# Power.net
KiCad netlist of a schematic drawn in Altium Designer
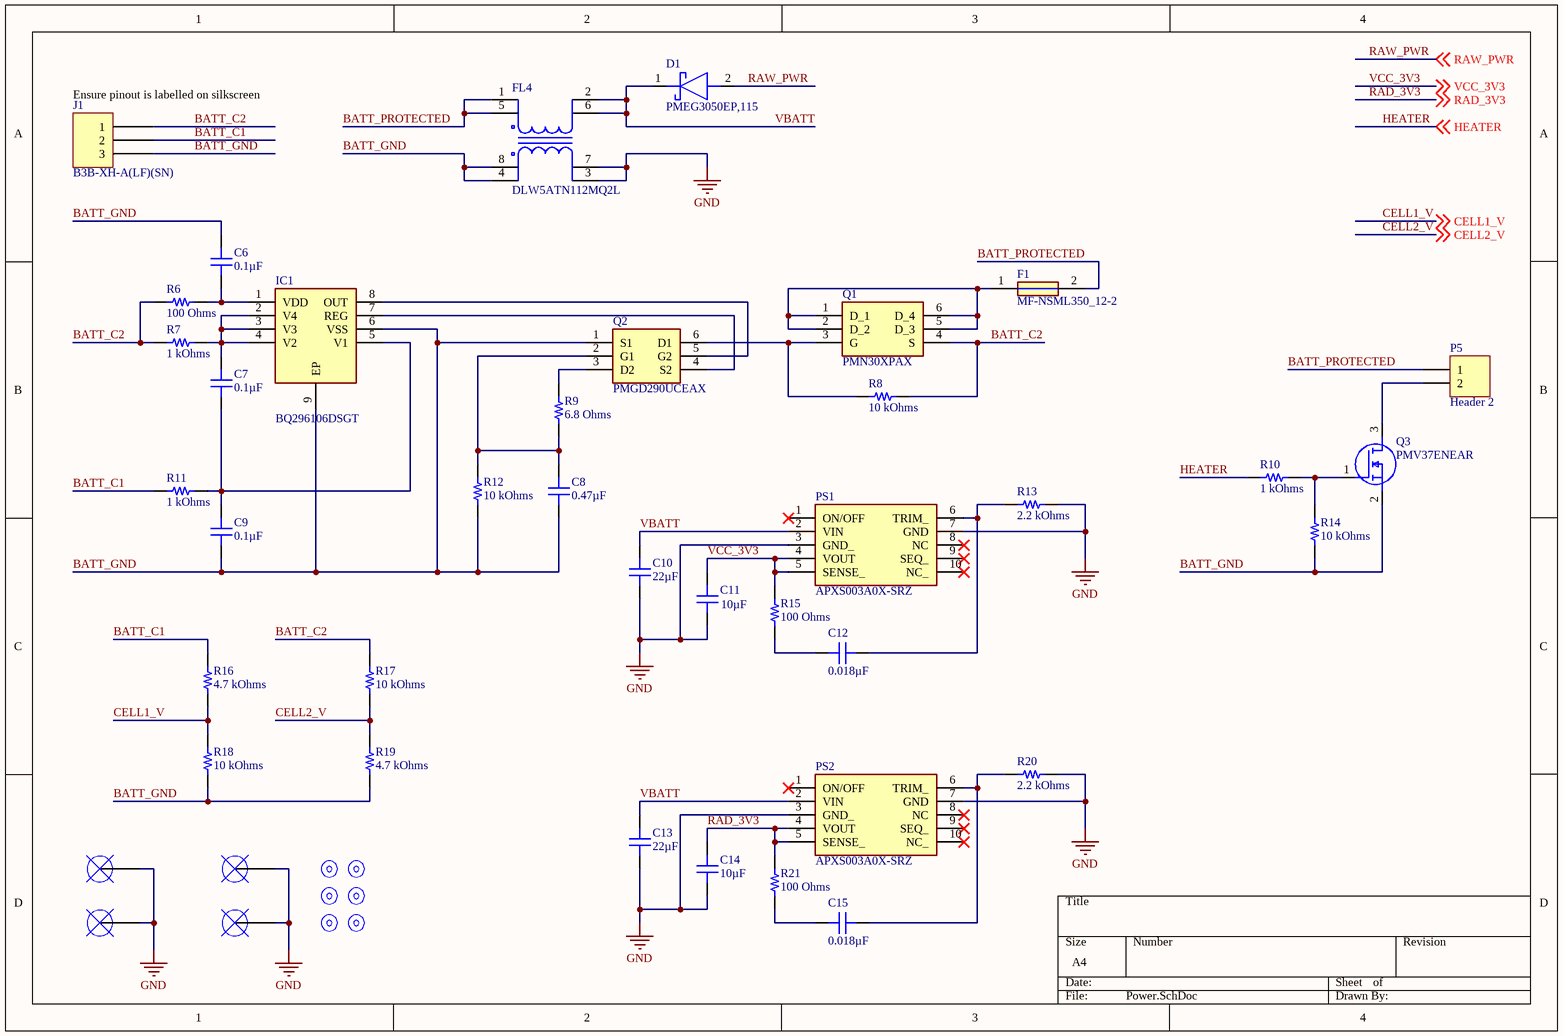
[diagram p0: Power.SchDoc]

(export (version "E")
  (design (tool "Eeschema 10.0.6"))
  (components
    (comp (ref "C6")
      (value "0.1µF")
      (footprint "CAP 0402_1005")
      (description "CAP CER 0.1UF 6.3V X5R 0402")
      (fields (field (name "PART NUMBER") "C0402C104K9PACTU") (field (name "MANUFACTURER") "KEMET"))
      (libsource (lib "Celestial Altium Library - altium_library") (part "Capacitor"))
    )
    (comp (ref "C7")
      (value "0.1µF")
      (footprint "CAP 0402_1005")
      (description "CAP CER 0.1UF 6.3V X5R 0402")
      (fields (field (name "PART NUMBER") "C0402C104K9PACTU") (field (name "MANUFACTURER") "KEMET"))
      (libsource (lib "Celestial Altium Library - altium_library") (part "Capacitor"))
    )
    (comp (ref "C8")
      (value "0.47µF")
      (footprint "CAP 0402_1005")
      (description "CAP CER 0.47UF 25V X5R 0402")
      (fields
        (field (name "PART NUMBER") "C1005X5R1E474K050BE")
        (field (name "MANUFACTURER") "TDK Corporation")
      )
      (libsource (lib "Celestial Altium Library - altium_library") (part "Capacitor"))
    )
    (comp (ref "C9")
      (value "0.1µF")
      (footprint "CAP 0402_1005")
      (description "CAP CER 0.1UF 6.3V X5R 0402")
      (fields (field (name "PART NUMBER") "C0402C104K9PACTU") (field (name "MANUFACTURER") "KEMET"))
      (libsource (lib "Celestial Altium Library - altium_library") (part "Capacitor"))
    )
    (comp (ref "C10")
      (value "22µF")
      (footprint "CAP 0805_2012")
      (description "CAP CER 22UF 16V X6S 0805")
      (fields
        (field (name "PART NUMBER") "C2012X6S1C226M125AC")
        (field (name "MANUFACTURER") "TDK Corporation")
      )
      (libsource (lib "Celestial Altium Library - altium_library") (part "Capacitor"))
    )
    (comp (ref "C11")
      (value "10µF")
      (footprint "CAP 0402_1005")
      (description "CAP CER 10UF 6.3V X5R 0402")
      (fields (field (name "PART NUMBER") "C0402C106M9PAC7867") (field (name "MANUFACTURER") "KEMET"))
      (libsource (lib "Celestial Altium Library - altium_library") (part "Capacitor"))
    )
    (comp (ref "C12")
      (value "0.018µF")
      (footprint "CAP 0402_1005")
      (description "CAP CER 0.018UF 25V X7R 0402")
      (fields (field (name "PART NUMBER") "CC0402KRX7R8BB183") (field (name "MANUFACTURER") "Yageo"))
      (libsource (lib "Celestial Altium Library - altium_library") (part "Capacitor"))
    )
    (comp (ref "C13")
      (value "22µF")
      (footprint "CAP 0805_2012")
      (description "CAP CER 22UF 16V X6S 0805")
      (fields
        (field (name "PART NUMBER") "C2012X6S1C226M125AC")
        (field (name "MANUFACTURER") "TDK Corporation")
      )
      (libsource (lib "Celestial Altium Library - altium_library") (part "Capacitor"))
    )
    (comp (ref "C14")
      (value "10µF")
      (footprint "CAP 0402_1005")
      (description "CAP CER 10UF 6.3V X5R 0402")
      (fields (field (name "PART NUMBER") "C0402C106M9PAC7867") (field (name "MANUFACTURER") "KEMET"))
      (libsource (lib "Celestial Altium Library - altium_library") (part "Capacitor"))
    )
    (comp (ref "C15")
      (value "0.018µF")
      (footprint "CAP 0402_1005")
      (description "CAP CER 0.018UF 25V X7R 0402")
      (fields (field (name "PART NUMBER") "CC0402KRX7R8BB183") (field (name "MANUFACTURER") "Yageo"))
      (libsource (lib "Celestial Altium Library - altium_library") (part "Capacitor"))
    )
    (comp (ref "D1")
      (value "PMEG3050EP,115")
      (footprint "SamacSys:PMEG3050EP115")
      (description "Schottky Diode")
      (libsource (lib "*") (part "PMEG3050EP,115"))
    )
    (comp (ref "F1")
      (value "MF-NSML350_12-2")
      (footprint "SamacSys:FUSC3216X140N")
      (description "Fuse")
      (fields (field (name "MANUFACTURER_PART_NUMBER") "MF-NSML350/12-2"))
      (libsource (lib "*") (part "MF-NSML350_12-2"))
    )
    (comp (ref "FL4")
      (value "DLW5ATN112MQ2L")
      (footprint "SamacSys:DLW5BSN302SQ2L")
      (description "Filter")
      (fields (field (name "MOUSER2 PART NUMBER") "81-DLW5ATN112MQ2L"))
      (libsource (lib "*") (part "DLW5ATN112MQ2L"))
    )
    (comp (ref "FM1")
      (value "1mm")
      (footprint "FIDUCIAL_MARK_ROUND")
      (description "Fiducial mark, width 1mm, clearance 3mm")
      (libsource (lib "VITA_57_FMC") (part "Fiducial_Mark"))
    )
    (comp (ref "FM2")
      (value "1mm")
      (footprint "FIDUCIAL_MARK_ROUND")
      (description "Fiducial mark, width 1mm, clearance 3mm")
      (libsource (lib "VITA_57_FMC") (part "Fiducial_Mark"))
    )
    (comp (ref "FM3")
      (value "1mm")
      (footprint "FIDUCIAL_MARK_ROUND")
      (description "Fiducial mark, width 1mm, clearance 3mm")
      (libsource (lib "VITA_57_FMC") (part "Fiducial_Mark"))
    )
    (comp (ref "FM4")
      (value "1mm")
      (footprint "FIDUCIAL_MARK_ROUND")
      (description "Fiducial mark, width 1mm, clearance 3mm")
      (libsource (lib "VITA_57_FMC") (part "Fiducial_Mark"))
    )
    (comp (ref "FM5")
      (value "1mm")
      (footprint "FIDUCIAL_MARK_ROUND")
      (description "Fiducial mark, width 1mm, clearance 3mm")
      (libsource (lib "VITA_57_FMC") (part "Fiducial_Mark"))
    )
    (comp (ref "FM6")
      (value "1mm")
      (footprint "FIDUCIAL_MARK_ROUND")
      (description "Fiducial mark, width 1mm, clearance 3mm")
      (libsource (lib "VITA_57_FMC") (part "Fiducial_Mark"))
    )
    (comp (ref "IC1")
      (value "BQ296106DSGT")
      (footprint "SamacSys:SON50P200X200X80-9N")
      (description "Integrated Circuit")
      (libsource (lib "*") (part "BQ296106DSGT"))
    )
    (comp (ref "J1")
      (value "B3B-XH-A(LF)(SN)")
      (footprint "JST XH B3B-XH-A")
      (description "CONN HEADER VERT 3POS 2.5MM")
      (fields (field (name "MANUFACTURER") "JST Sales America Inc."))
      (libsource (lib "Celestial Altium Library - altium_library") (part "3 Pin"))
    )
    (comp (ref "MH1")
      (value "2.7mm")
      (footprint "Mounting_Hole_Plated_2.7mm-COVERED")
      (description "Mounting hole, hole size 2.7mm")
      (libsource (lib "VITA_57_FMC") (part "Mounting_Hole_2.7mm"))
    )
    (comp (ref "MH2")
      (value "2.7mm")
      (footprint "Mounting_Hole_Plated_2.7mm-COVERED")
      (description "Mounting hole, hole size 2.7mm")
      (libsource (lib "VITA_57_FMC") (part "Mounting_Hole_2.7mm"))
    )
    (comp (ref "MH3")
      (value "2.7mm")
      (footprint "Mounting_Hole_Plated_2.7mm-COVERED")
      (description "Mounting hole, hole size 2.7mm")
      (libsource (lib "VITA_57_FMC") (part "Mounting_Hole_2.7mm"))
    )
    (comp (ref "MH4")
      (value "2.7mm")
      (footprint "Mounting_Hole_Plated_2.7mm-COVERED")
      (description "Mounting hole, hole size 2.7mm")
      (libsource (lib "VITA_57_FMC") (part "Mounting_Hole_2.7mm"))
    )
    (comp (ref "P5")
      (value "Header 2")
      (footprint "HDR1X2")
      (description "Header, 2-Pin")
      (fields (field (name "PUBLISHER") "Altium Limited"))
      (libsource (lib "Miscellaneous Connectors") (part "Header 2"))
    )
    (comp (ref "PS1")
      (value "APXS003A0X-SRZ")
      (footprint "APTH003A0XSRZ")
      (description "Power Supply")
      (libsource (lib "SamacSys") (part "APXS003A0X-SRZ"))
    )
    (comp (ref "PS2")
      (value "APXS003A0X-SRZ")
      (footprint "APTH003A0XSRZ")
      (description "Power Supply")
      (libsource (lib "SamacSys") (part "APXS003A0X-SRZ"))
    )
    (comp (ref "Q1")
      (value "PMN30XPAX")
      (footprint "SamacSys:SOT95P275X110-6N")
      (description "MOSFET (P-Channel)")
      (libsource (lib "*") (part "PMN30XPAX"))
    )
    (comp (ref "Q2")
      (value "PMGD290UCEAX")
      (footprint "SamacSys:SOT65P210X110-6N")
      (description "Transistor")
      (libsource (lib "*") (part "PMGD290UCEAX"))
    )
    (comp (ref "Q3")
      (value "PMV37ENEAR")
      (footprint "SamacSys:SOT95P230X110-3N")
      (description "MOSFET (N-Channel)")
      (libsource (lib "*") (part "PMV37ENEAR"))
    )
    (comp (ref "R6")
      (value "100 Ohms")
      (footprint "RES 0402_1005")
      (description "RES SMD 100 OHM 1% 1/16W 0402")
      (fields
        (field (name "PART NUMBER") "CRG0402F100R")
        (field (name "MANUFACTURER") "TE Connectivity Passive Product")
      )
      (libsource (lib "Celestial Altium Library - altium_library") (part "Resistor"))
    )
    (comp (ref "R7")
      (value "1 kOhms")
      (footprint "RES 0402_1005")
      (description "RES SMD 1K OHM 1% 1/16W 0402")
      (fields (field (name "PART NUMBER") "CRCW04021K00FKEDC") (field (name "MANUFACTURER") "Vishay Dale"))
      (libsource (lib "Celestial Altium Library - altium_library") (part "Resistor"))
    )
    (comp (ref "R8")
      (value "10 kOhms")
      (footprint "RES 0402_1005")
      (description "RES SMD 10K OHM 0.1% 1/16W 0402")
      (fields
        (field (name "PART NUMBER") "CPF0402B10KE1")
        (field (name "MANUFACTURER") "TE Connectivity Passive Product")
      )
      (libsource (lib "Celestial Altium Library - altium_library") (part "Resistor"))
    )
    (comp (ref "R9")
      (value "6.8 Ohms")
      (footprint "RES 0402_1005")
      (description "RES SMD 6.8 OHM 5% 1/10W 0402")
      (fields
        (field (name "PART NUMBER") "ERJ-2GEJ6R8X")
        (field (name "MANUFACTURER") "Panasonic Electronic Components")
      )
      (libsource (lib "Celestial Altium Library - altium_library") (part "Resistor"))
    )
    (comp (ref "R10")
      (value "1 kOhms")
      (footprint "RES 0402_1005")
      (description "RES SMD 1K OHM 1% 1/16W 0402")
      (fields (field (name "PART NUMBER") "CRCW04021K00FKEDC") (field (name "MANUFACTURER") "Vishay Dale"))
      (libsource (lib "Celestial Altium Library - altium_library") (part "Resistor"))
    )
    (comp (ref "R11")
      (value "1 kOhms")
      (footprint "RES 0402_1005")
      (description "RES SMD 1K OHM 1% 1/16W 0402")
      (fields (field (name "PART NUMBER") "CRCW04021K00FKEDC") (field (name "MANUFACTURER") "Vishay Dale"))
      (libsource (lib "Celestial Altium Library - altium_library") (part "Resistor"))
    )
    (comp (ref "R12")
      (value "10 kOhms")
      (footprint "RES 0402_1005")
      (description "RES SMD 10K OHM 0.1% 1/16W 0402")
      (fields
        (field (name "PART NUMBER") "CPF0402B10KE1")
        (field (name "MANUFACTURER") "TE Connectivity Passive Product")
      )
      (libsource (lib "Celestial Altium Library - altium_library") (part "Resistor"))
    )
    (comp (ref "R13")
      (value "2.2 kOhms")
      (footprint "RES 0402_1005")
      (description "RES SMD 2.2K OHM 0.1% 1/16W 0402")
      (fields
        (field (name "PART NUMBER") "CPF0402B2K2E1")
        (field (name "MANUFACTURER") "TE Connectivity Passive Product")
      )
      (libsource (lib "Celestial Altium Library - altium_library") (part "Resistor"))
    )
    (comp (ref "R14")
      (value "10 kOhms")
      (footprint "RES 0402_1005")
      (description "RES SMD 10K OHM 0.1% 1/16W 0402")
      (fields
        (field (name "PART NUMBER") "CPF0402B10KE1")
        (field (name "MANUFACTURER") "TE Connectivity Passive Product")
      )
      (libsource (lib "Celestial Altium Library - altium_library") (part "Resistor"))
    )
    (comp (ref "R15")
      (value "100 Ohms")
      (footprint "RES 0402_1005")
      (description "RES SMD 100 OHM 1% 1/16W 0402")
      (fields
        (field (name "PART NUMBER") "CRG0402F100R")
        (field (name "MANUFACTURER") "TE Connectivity Passive Product")
      )
      (libsource (lib "Celestial Altium Library - altium_library") (part "Resistor"))
    )
    (comp (ref "R16")
      (value "4.7 kOhms")
      (footprint "RES 0402_1005")
      (description "RES SMD 4.7K OHM 5% 1/16W 0402")
      (fields (field (name "PART NUMBER") "CRCW04024K70JNEDC") (field (name "MANUFACTURER") "Vishay Dale"))
      (libsource (lib "Celestial Altium Library - altium_library") (part "Resistor"))
    )
    (comp (ref "R17")
      (value "10 kOhms")
      (footprint "RES 0402_1005")
      (description "RES SMD 10K OHM 0.1% 1/16W 0402")
      (fields
        (field (name "PART NUMBER") "CPF0402B10KE1")
        (field (name "MANUFACTURER") "TE Connectivity Passive Product")
      )
      (libsource (lib "Celestial Altium Library - altium_library") (part "Resistor"))
    )
    (comp (ref "R18")
      (value "10 kOhms")
      (footprint "RES 0402_1005")
      (description "RES SMD 10K OHM 0.1% 1/16W 0402")
      (fields
        (field (name "PART NUMBER") "CPF0402B10KE1")
        (field (name "MANUFACTURER") "TE Connectivity Passive Product")
      )
      (libsource (lib "Celestial Altium Library - altium_library") (part "Resistor"))
    )
    (comp (ref "R19")
      (value "4.7 kOhms")
      (footprint "RES 0402_1005")
      (description "RES SMD 4.7K OHM 5% 1/16W 0402")
      (fields (field (name "PART NUMBER") "CRCW04024K70JNEDC") (field (name "MANUFACTURER") "Vishay Dale"))
      (libsource (lib "Celestial Altium Library - altium_library") (part "Resistor"))
    )
    (comp (ref "R20")
      (value "2.2 kOhms")
      (footprint "RES 0402_1005")
      (description "RES SMD 2.2K OHM 0.1% 1/16W 0402")
      (fields
        (field (name "PART NUMBER") "CPF0402B2K2E1")
        (field (name "MANUFACTURER") "TE Connectivity Passive Product")
      )
      (libsource (lib "Celestial Altium Library - altium_library") (part "Resistor"))
    )
    (comp (ref "R21")
      (value "100 Ohms")
      (footprint "RES 0402_1005")
      (description "RES SMD 100 OHM 1% 1/16W 0402")
      (fields
        (field (name "PART NUMBER") "CRG0402F100R")
        (field (name "MANUFACTURER") "TE Connectivity Passive Product")
      )
      (libsource (lib "Celestial Altium Library - altium_library") (part "Resistor"))
    )
  )
  (nets
    (net (code "1") (name "/BATT_C1") (class "Default")
      (node (ref "J1") (pin "2") (pinfunction "2_2") (pintype "passive"))
      (node (ref "R11") (pin "1") (pinfunction "1_1") (pintype "passive"))
      (node (ref "R16") (pin "2") (pinfunction "2_2") (pintype "passive"))
    )
    (net (code "2") (name "/BATT_C2") (class "Default")
      (node (ref "J1") (pin "1") (pinfunction "1_1") (pintype "passive"))
      (node (ref "Q1") (pin "4") (pinfunction "S_4") (pintype "passive"))
      (node (ref "R17") (pin "1") (pinfunction "1_1") (pintype "passive"))
      (node (ref "R6") (pin "2") (pinfunction "2_2") (pintype "passive"))
      (node (ref "R7") (pin "1") (pinfunction "1_1") (pintype "passive"))
      (node (ref "R8") (pin "1") (pinfunction "1_1") (pintype "passive"))
    )
    (net (code "3") (name "/BATT_GND") (class "Default")
      (node (ref "C6") (pin "2") (pinfunction "2_2") (pintype "passive"))
      (node (ref "C8") (pin "1") (pinfunction "1_1") (pintype "passive"))
      (node (ref "C9") (pin "1") (pinfunction "1_1") (pintype "passive"))
      (node (ref "FL4") (pin "4") (pinfunction "4_4") (pintype "passive"))
      (node (ref "FL4") (pin "8") (pinfunction "8_8") (pintype "passive"))
      (node (ref "IC1") (pin "6") (pinfunction "VSS_6") (pintype "passive"))
      (node (ref "IC1") (pin "9") (pinfunction "EP_9") (pintype "passive"))
      (node (ref "J1") (pin "3") (pinfunction "3_3") (pintype "passive"))
      (node (ref "Q2") (pin "1") (pinfunction "S1_1") (pintype "passive"))
      (node (ref "Q3") (pin "2") (pinfunction "S_2") (pintype "passive"))
      (node (ref "R12") (pin "2") (pinfunction "2_2") (pintype "passive"))
      (node (ref "R14") (pin "2") (pinfunction "2_2") (pintype "passive"))
      (node (ref "R18") (pin "2") (pinfunction "2_2") (pintype "passive"))
      (node (ref "R19") (pin "1") (pinfunction "1_1") (pintype "passive"))
    )
    (net (code "4") (name "/BATT_PROTECTED") (class "Default")
      (node (ref "F1") (pin "2") (pinfunction "2_2") (pintype "passive"))
      (node (ref "FL4") (pin "1") (pinfunction "1_1") (pintype "passive"))
      (node (ref "FL4") (pin "5") (pinfunction "5_5") (pintype "passive"))
      (node (ref "P5") (pin "1") (pinfunction "1_1") (pintype "passive"))
    )
    (net (code "5") (name "/VBATT") (class "Default")
      (node (ref "C10") (pin "2") (pinfunction "2_2") (pintype "passive"))
      (node (ref "C13") (pin "2") (pinfunction "2_2") (pintype "passive"))
      (node (ref "D1") (pin "1") (pinfunction "K_1") (pintype "passive"))
      (node (ref "FL4") (pin "2") (pinfunction "2_2") (pintype "passive"))
      (node (ref "FL4") (pin "6") (pinfunction "6_6") (pintype "passive"))
      (node (ref "PS1") (pin "2") (pinfunction "VIN_2") (pintype "passive"))
      (node (ref "PS2") (pin "2") (pinfunction "VIN_2") (pintype "passive"))
    )
    (net (code "6") (name "CELL1_V") (class "Default")
      (node (ref "R16") (pin "1") (pinfunction "1_1") (pintype "passive"))
      (node (ref "R18") (pin "1") (pinfunction "1_1") (pintype "passive"))
    )
    (net (code "7") (name "CELL2_V") (class "Default")
      (node (ref "R17") (pin "2") (pinfunction "2_2") (pintype "passive"))
      (node (ref "R19") (pin "2") (pinfunction "2_2") (pintype "passive"))
    )
    (net (code "8") (name "GND") (class "Default")
      (node (ref "C10") (pin "1") (pinfunction "1_1") (pintype "passive"))
      (node (ref "C11") (pin "1") (pinfunction "1_1") (pintype "passive"))
      (node (ref "C13") (pin "1") (pinfunction "1_1") (pintype "passive"))
      (node (ref "C14") (pin "1") (pinfunction "1_1") (pintype "passive"))
      (node (ref "FL4") (pin "3") (pinfunction "3_3") (pintype "passive"))
      (node (ref "FL4") (pin "7") (pinfunction "7_7") (pintype "passive"))
      (node (ref "MH1") (pin "0") (pinfunction "0_0") (pintype "passive"))
      (node (ref "MH2") (pin "0") (pinfunction "0_0") (pintype "passive"))
      (node (ref "MH3") (pin "0") (pinfunction "0_0") (pintype "passive"))
      (node (ref "MH4") (pin "0") (pinfunction "0_0") (pintype "passive"))
      (node (ref "PS1") (pin "3") (pinfunction "GND__3") (pintype "passive"))
      (node (ref "PS1") (pin "7") (pinfunction "GND_7") (pintype "passive"))
      (node (ref "PS2") (pin "3") (pinfunction "GND__3") (pintype "passive"))
      (node (ref "PS2") (pin "7") (pinfunction "GND_7") (pintype "passive"))
      (node (ref "R13") (pin "1") (pinfunction "1_1") (pintype "passive"))
      (node (ref "R20") (pin "2") (pinfunction "2_2") (pintype "passive"))
    )
    (net (code "9") (name "HEATER") (class "Default")
      (node (ref "R10") (pin "1") (pinfunction "1_1") (pintype "passive"))
    )
    (net (code "10") (name "Net-(C12-Pad1)") (class "Default")
      (node (ref "C12") (pin "1") (pinfunction "1_1") (pintype "passive"))
      (node (ref "R15") (pin "2") (pinfunction "2_2") (pintype "passive"))
    )
    (net (code "11") (name "Net-(C15-Pad1)") (class "Default")
      (node (ref "C15") (pin "1") (pinfunction "1_1") (pintype "passive"))
      (node (ref "R21") (pin "2") (pinfunction "2_2") (pintype "passive"))
    )
    (net (code "12") (name "Net-(IC1-OUT)") (class "Default")
      (node (ref "IC1") (pin "8") (pinfunction "OUT_8") (pintype "passive"))
      (node (ref "Q2") (pin "5") (pinfunction "G2_5") (pintype "passive"))
    )
    (net (code "13") (name "Net-(IC1-REG)") (class "Default")
      (node (ref "IC1") (pin "7") (pinfunction "REG_7") (pintype "passive"))
      (node (ref "Q2") (pin "4") (pinfunction "S2_4") (pintype "passive"))
    )
    (net (code "14") (name "Net-(IC1-V1)") (class "Default")
      (node (ref "C7") (pin "1") (pinfunction "1_1") (pintype "passive"))
      (node (ref "C9") (pin "2") (pinfunction "2_2") (pintype "passive"))
      (node (ref "IC1") (pin "5") (pinfunction "V1_5") (pintype "passive"))
      (node (ref "R11") (pin "2") (pinfunction "2_2") (pintype "passive"))
    )
    (net (code "15") (name "Net-(IC1-V2)") (class "Default")
      (node (ref "C7") (pin "2") (pinfunction "2_2") (pintype "passive"))
      (node (ref "IC1") (pin "2") (pinfunction "V4_2") (pintype "passive"))
      (node (ref "IC1") (pin "3") (pinfunction "V3_3") (pintype "passive"))
      (node (ref "IC1") (pin "4") (pinfunction "V2_4") (pintype "passive"))
      (node (ref "R7") (pin "2") (pinfunction "2_2") (pintype "passive"))
    )
    (net (code "16") (name "Net-(IC1-VDD)") (class "Default")
      (node (ref "C6") (pin "1") (pinfunction "1_1") (pintype "passive"))
      (node (ref "IC1") (pin "1") (pinfunction "VDD_1") (pintype "passive"))
      (node (ref "R6") (pin "1") (pinfunction "1_1") (pintype "passive"))
    )
    (net (code "17") (name "Net-(PS1-TRIM_)") (class "Default")
      (node (ref "C12") (pin "2") (pinfunction "2_2") (pintype "passive"))
      (node (ref "PS1") (pin "6") (pinfunction "TRIM__6") (pintype "passive"))
      (node (ref "R13") (pin "2") (pinfunction "2_2") (pintype "passive"))
    )
    (net (code "18") (name "Net-(PS2-TRIM_)") (class "Default")
      (node (ref "C15") (pin "2") (pinfunction "2_2") (pintype "passive"))
      (node (ref "PS2") (pin "6") (pinfunction "TRIM__6") (pintype "passive"))
      (node (ref "R20") (pin "1") (pinfunction "1_1") (pintype "passive"))
    )
    (net (code "19") (name "Net-(Q1-D_1)") (class "Default")
      (node (ref "F1") (pin "1") (pinfunction "1_1") (pintype "passive"))
      (node (ref "Q1") (pin "1") (pinfunction "D_1_1") (pintype "passive"))
      (node (ref "Q1") (pin "2") (pinfunction "D_2_2") (pintype "passive"))
      (node (ref "Q1") (pin "5") (pinfunction "D_3_5") (pintype "passive"))
      (node (ref "Q1") (pin "6") (pinfunction "D_4_6") (pintype "passive"))
    )
    (net (code "20") (name "Net-(Q1-G)") (class "Default")
      (node (ref "Q1") (pin "3") (pinfunction "G_3") (pintype "passive"))
      (node (ref "Q2") (pin "6") (pinfunction "D1_6") (pintype "passive"))
      (node (ref "R8") (pin "2") (pinfunction "2_2") (pintype "passive"))
    )
    (net (code "21") (name "Net-(Q2-D2)") (class "Default")
      (node (ref "Q2") (pin "3") (pinfunction "D2_3") (pintype "passive"))
      (node (ref "R9") (pin "2") (pinfunction "2_2") (pintype "passive"))
    )
    (net (code "22") (name "Net-(Q2-G1)") (class "Default")
      (node (ref "C8") (pin "2") (pinfunction "2_2") (pintype "passive"))
      (node (ref "Q2") (pin "2") (pinfunction "G1_2") (pintype "passive"))
      (node (ref "R12") (pin "1") (pinfunction "1_1") (pintype "passive"))
      (node (ref "R9") (pin "1") (pinfunction "1_1") (pintype "passive"))
    )
    (net (code "23") (name "Net-(Q3-D)") (class "Default")
      (node (ref "P5") (pin "2") (pinfunction "2_2") (pintype "passive"))
      (node (ref "Q3") (pin "3") (pinfunction "D_3") (pintype "passive"))
    )
    (net (code "24") (name "Net-(Q3-G)") (class "Default")
      (node (ref "Q3") (pin "1") (pinfunction "G_1") (pintype "passive"))
      (node (ref "R10") (pin "2") (pinfunction "2_2") (pintype "passive"))
      (node (ref "R14") (pin "1") (pinfunction "1_1") (pintype "passive"))
    )
    (net (code "25") (name "RAD_3V3") (class "Default")
      (node (ref "C14") (pin "2") (pinfunction "2_2") (pintype "passive"))
      (node (ref "PS2") (pin "4") (pinfunction "VOUT_4") (pintype "passive"))
      (node (ref "PS2") (pin "5") (pinfunction "SENSE__5") (pintype "passive"))
      (node (ref "R21") (pin "1") (pinfunction "1_1") (pintype "passive"))
    )
    (net (code "26") (name "RAW_PWR") (class "Default")
      (node (ref "D1") (pin "2") (pinfunction "A_2") (pintype "passive"))
    )
    (net (code "27") (name "VCC_3V3") (class "Default")
      (node (ref "C11") (pin "2") (pinfunction "2_2") (pintype "passive"))
      (node (ref "PS1") (pin "4") (pinfunction "VOUT_4") (pintype "passive"))
      (node (ref "PS1") (pin "5") (pinfunction "SENSE__5") (pintype "passive"))
      (node (ref "R15") (pin "1") (pinfunction "1_1") (pintype "passive"))
    )
    (net (code "28") (name "unconnected-(FM1-PadFD0)") (class "Default")
      (node (ref "FM1") (pin "FD0") (pinfunction "FD0_FD0") (pintype "passive"))
    )
    (net (code "29") (name "unconnected-(FM2-PadFD0)") (class "Default")
      (node (ref "FM2") (pin "FD0") (pinfunction "FD0_FD0") (pintype "passive"))
    )
    (net (code "30") (name "unconnected-(FM3-PadFD0)") (class "Default")
      (node (ref "FM3") (pin "FD0") (pinfunction "FD0_FD0") (pintype "passive"))
    )
    (net (code "31") (name "unconnected-(FM4-PadFD0)") (class "Default")
      (node (ref "FM4") (pin "FD0") (pinfunction "FD0_FD0") (pintype "passive"))
    )
    (net (code "32") (name "unconnected-(FM5-PadFD0)") (class "Default")
      (node (ref "FM5") (pin "FD0") (pinfunction "FD0_FD0") (pintype "passive"))
    )
    (net (code "33") (name "unconnected-(FM6-PadFD0)") (class "Default")
      (node (ref "FM6") (pin "FD0") (pinfunction "FD0_FD0") (pintype "passive"))
    )
    (net (code "34") (name "unconnected-(PS1-NC-Pad8)") (class "Default")
      (node (ref "PS1") (pin "8") (pinfunction "NC_8") (pintype "passive+no_connect"))
    )
    (net (code "35") (name "unconnected-(PS1-NC_-Pad10)") (class "Default")
      (node (ref "PS1") (pin "10") (pinfunction "NC__10") (pintype "passive+no_connect"))
    )
    (net (code "36") (name "unconnected-(PS1-ON{slash}OFF-Pad1)") (class "Default")
      (node (ref "PS1") (pin "1") (pinfunction "ON/OFF_1") (pintype "passive+no_connect"))
    )
    (net (code "37") (name "unconnected-(PS1-SEQ_-Pad9)") (class "Default")
      (node (ref "PS1") (pin "9") (pinfunction "SEQ__9") (pintype "passive+no_connect"))
    )
    (net (code "38") (name "unconnected-(PS2-NC-Pad8)") (class "Default")
      (node (ref "PS2") (pin "8") (pinfunction "NC_8") (pintype "passive+no_connect"))
    )
    (net (code "39") (name "unconnected-(PS2-NC_-Pad10)") (class "Default")
      (node (ref "PS2") (pin "10") (pinfunction "NC__10") (pintype "passive+no_connect"))
    )
    (net (code "40") (name "unconnected-(PS2-ON{slash}OFF-Pad1)") (class "Default")
      (node (ref "PS2") (pin "1") (pinfunction "ON/OFF_1") (pintype "passive+no_connect"))
    )
    (net (code "41") (name "unconnected-(PS2-SEQ_-Pad9)") (class "Default")
      (node (ref "PS2") (pin "9") (pinfunction "SEQ__9") (pintype "passive+no_connect"))
    )
  )
)
